# pc_healthypi_move_nRF5340_v3.net
KiCad netlist of a schematic drawn in EAGLE
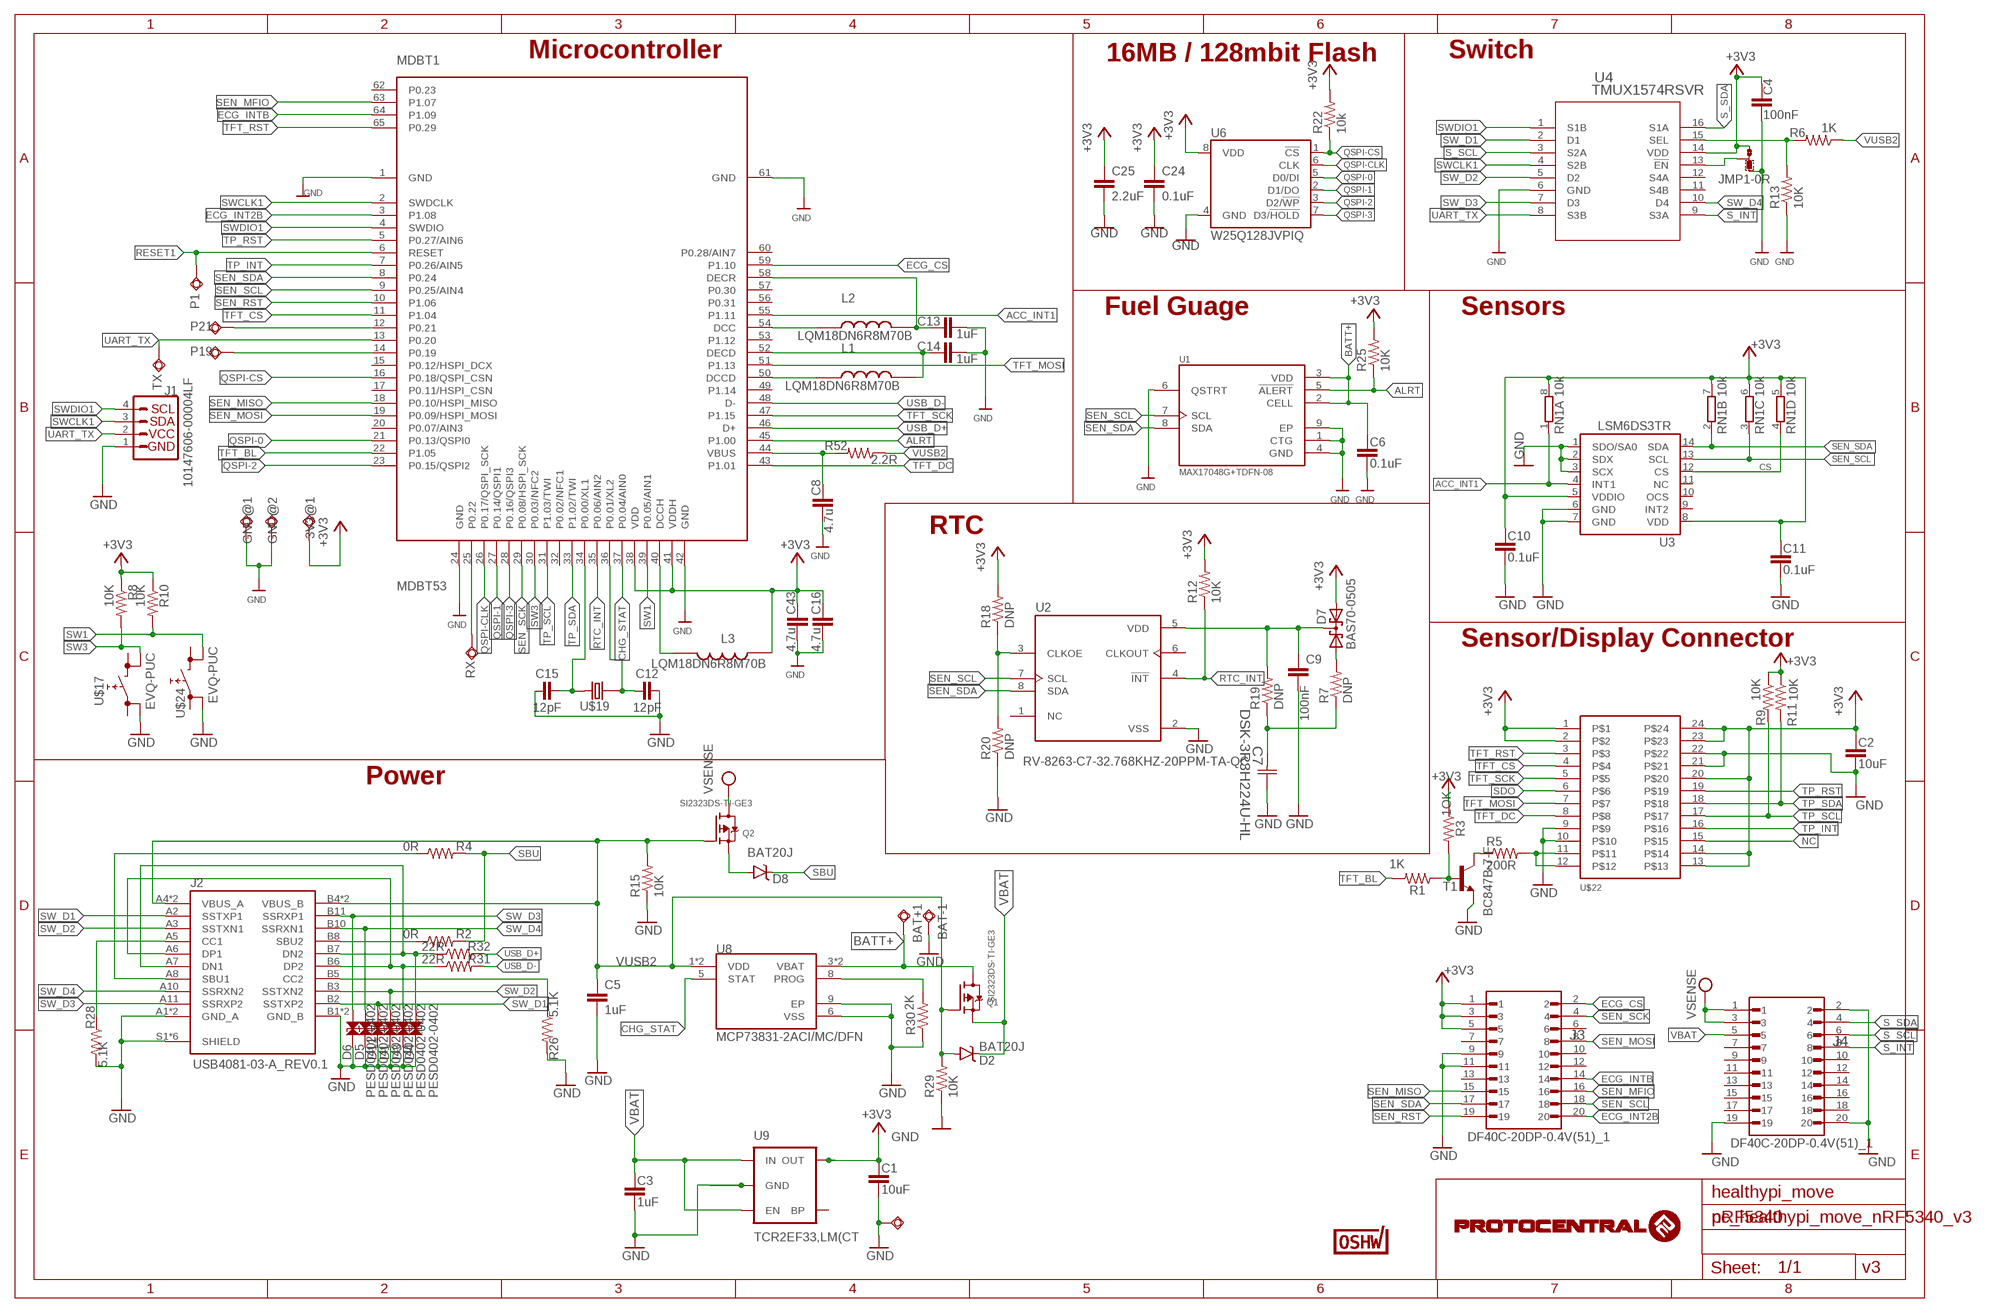
[diagram p0: schematic, sheet 1]

(export (version "E")
  (design (tool "Eeschema 10.0.6"))
  (components
    (comp (ref "3V3@1")
      (value "TPSQTP13SQ")
      (footprint "eagle-import:TP13SQ")
      (libsource (lib "eagle-import") (part "TPSQTP13SQ"))
    )
    (comp (ref "BAT+1")
      (value "TPSQTP13SQ")
      (footprint "eagle-import:TP13SQ")
      (libsource (lib "eagle-import") (part "TPSQTP13SQ"))
    )
    (comp (ref "BAT-1")
      (value "TPSQTP13SQ")
      (footprint "eagle-import:TP13SQ")
      (libsource (lib "eagle-import") (part "TPSQTP13SQ"))
    )
    (comp (ref "C1")
      (value "10uF")
      (footprint "eagle-import:0603@1")
      (libsource (lib "eagle-import") (part "0.1UF-0603-100V-10%"))
    )
    (comp (ref "C2")
      (value "10uF")
      (footprint "eagle-import:0603@1")
      (libsource (lib "eagle-import") (part "0.1UF-0603-100V-10%"))
    )
    (comp (ref "C3")
      (value "1uF")
      (footprint "eagle-import:0402-TIGHT")
      (libsource (lib "eagle-import") (part "0.1UF-0402T-6.3V-10%-X7R"))
    )
    (comp (ref "C4")
      (value "100nF")
      (footprint "eagle-import:0402-TIGHT")
      (libsource (lib "eagle-import") (part "2.2UF-0402_TIGHT-10V-10%-X5R"))
    )
    (comp (ref "C5")
      (value "1uF")
      (footprint "eagle-import:0402-TIGHT")
      (libsource (lib "eagle-import") (part "2.2UF-0402_TIGHT-10V-10%-X5R"))
    )
    (comp (ref "C6")
      (value "0.1uF")
      (footprint "eagle-import:0402-TIGHT")
      (libsource (lib "eagle-import") (part "0.1UF-0402T-6.3V-10%-X7R"))
    )
    (comp (ref "C7")
      (value "DSK-3R3H224U-HL")
      (footprint "eagle-import:CAP_DSK-3R3H224U-HL_ELN")
      (fields (field (name "COPYRIGHT") "Copyright (C) 2023 Ultra Librarian. All rights reserved."))
      (libsource (lib "eagle-import") (part "DSK-3R3H224U-HL"))
    )
    (comp (ref "C8")
      (value "4.7u")
      (footprint "eagle-import:C0402")
      (libsource (lib "eagle-import") (part "C-EUC0402"))
    )
    (comp (ref "C9")
      (value "100nF")
      (footprint "eagle-import:C0402")
      (libsource (lib "eagle-import") (part "C-EUC0402"))
    )
    (comp (ref "C10")
      (value "0.1uF")
      (footprint "eagle-import:0402-TIGHT")
      (libsource (lib "eagle-import") (part "0.1UF-0402T-6.3V-10%-X7R"))
    )
    (comp (ref "C11")
      (value "0.1uF")
      (footprint "eagle-import:0402-TIGHT")
      (libsource (lib "eagle-import") (part "0.1UF-0402T-6.3V-10%-X7R"))
    )
    (comp (ref "C12")
      (value "12pF")
      (footprint "eagle-import:C0402")
      (libsource (lib "eagle-import") (part "CAPACITORS-0402"))
    )
    (comp (ref "C13")
      (value "1uF")
      (footprint "eagle-import:0402-TIGHT")
      (libsource (lib "eagle-import") (part "2.2UF-0402_TIGHT-10V-10%-X5R"))
    )
    (comp (ref "C14")
      (value "1uF")
      (footprint "eagle-import:0402-TIGHT")
      (libsource (lib "eagle-import") (part "2.2UF-0402_TIGHT-10V-10%-X5R"))
    )
    (comp (ref "C15")
      (value "12pF")
      (footprint "eagle-import:C0402")
      (libsource (lib "eagle-import") (part "CAPACITORS-0402"))
    )
    (comp (ref "C16")
      (value "4.7u")
      (footprint "eagle-import:C0402")
      (libsource (lib "eagle-import") (part "C-EUC0402"))
    )
    (comp (ref "C24")
      (value "0.1uF")
      (footprint "eagle-import:0402-TIGHT")
      (libsource (lib "eagle-import") (part "0.1UF-0402T-6.3V-10%-X7R"))
    )
    (comp (ref "C25")
      (value "2.2uF")
      (footprint "eagle-import:0402-TIGHT")
      (libsource (lib "eagle-import") (part "2.2UF-0402_TIGHT-10V-10%-X5R"))
    )
    (comp (ref "C43")
      (value "4.7u")
      (footprint "eagle-import:C0402")
      (libsource (lib "eagle-import") (part "C-EUC0402"))
    )
    (comp (ref "D1")
      (value "PESD0402-0402")
      (footprint "eagle-import:0402")
      (fields
        (field (name "DIGIKEY_PART") "PESD0402-140CT-ND")
        (field (name "MOUSE_PART") "650-PESD0402-140")
      )
      (libsource (lib "eagle-import") (part "PESD0402-0402"))
    )
    (comp (ref "D2")
      (value "BAT20J")
      (footprint "eagle-import:SOD-323")
      (libsource (lib "eagle-import") (part "DIODE-SCHOTTKY-BAT20J"))
    )
    (comp (ref "D3")
      (value "PESD0402-0402")
      (footprint "eagle-import:0402")
      (fields
        (field (name "DIGIKEY_PART") "PESD0402-140CT-ND")
        (field (name "MOUSE_PART") "650-PESD0402-140")
      )
      (libsource (lib "eagle-import") (part "PESD0402-0402"))
    )
    (comp (ref "D4")
      (value "PESD0402-0402")
      (footprint "eagle-import:0402")
      (fields
        (field (name "DIGIKEY_PART") "PESD0402-140CT-ND")
        (field (name "MOUSE_PART") "650-PESD0402-140")
      )
      (libsource (lib "eagle-import") (part "PESD0402-0402"))
    )
    (comp (ref "D5")
      (value "PESD0402-0402")
      (footprint "eagle-import:0402")
      (fields
        (field (name "DIGIKEY_PART") "PESD0402-140CT-ND")
        (field (name "MOUSE_PART") "650-PESD0402-140")
      )
      (libsource (lib "eagle-import") (part "PESD0402-0402"))
    )
    (comp (ref "D6")
      (value "PESD0402-0402")
      (footprint "eagle-import:0402")
      (fields
        (field (name "DIGIKEY_PART") "PESD0402-140CT-ND")
        (field (name "MOUSE_PART") "650-PESD0402-140")
      )
      (libsource (lib "eagle-import") (part "PESD0402-0402"))
    )
    (comp (ref "D7")
      (value "BAS70-0505")
      (footprint "eagle-import:SOT23")
      (fields (field (name "MF") "Diotec") (field (name "MP") "BAS70-05"))
      (libsource (lib "eagle-import") (part "BAS70-0505"))
    )
    (comp (ref "D8")
      (value "BAT20J")
      (footprint "eagle-import:SOD-323")
      (libsource (lib "eagle-import") (part "DIODE-SCHOTTKY-BAT20J"))
    )
    (comp (ref "D11")
      (value "PESD0402-0402")
      (footprint "eagle-import:0402")
      (fields
        (field (name "DIGIKEY_PART") "PESD0402-140CT-ND")
        (field (name "MOUSE_PART") "650-PESD0402-140")
      )
      (libsource (lib "eagle-import") (part "PESD0402-0402"))
    )
    (comp (ref "GND@1")
      (value "TPSQTP13SQ")
      (footprint "eagle-import:TP13SQ")
      (libsource (lib "eagle-import") (part "TPSQTP13SQ"))
    )
    (comp (ref "GND@2")
      (value "TPSQTP13SQ")
      (footprint "eagle-import:TP13SQ")
      (libsource (lib "eagle-import") (part "TPSQTP13SQ"))
    )
    (comp (ref "J1")
      (value "10147606-00004LF")
      (footprint "eagle-import:JST04_1MM_RA")
      (libsource (lib "eagle-import") (part "QWIIC_CONNECTORJS-1MM"))
    )
    (comp (ref "J2")
      (value "USB4081-03-A_REV0.1")
      (footprint "eagle-import:GCT_USB4081-03-A_REV0.1")
      (fields (field (name "MF") "Global Connector Technology") (field (name "MP") "USB4081-03-A"))
      (libsource (lib "eagle-import") (part "USB4081-03-A_REV0.1"))
    )
    (comp (ref "J3")
      (value "DF40C-20DP-0.4V(51)_1")
      (footprint "eagle-import:HRS_DF40C-20DP-0.4V(51)")
      (fields (field (name "MANUFACTURER") "Hirose Electric"))
      (libsource (lib "eagle-import") (part "DF40C-20DP-0.4V(51)_1"))
    )
    (comp (ref "J4")
      (value "DF40C-20DP-0.4V(51)_1")
      (footprint "eagle-import:HRS_DF40C-20DP-0.4V(51)")
      (fields (field (name "MANUFACTURER") "Hirose Electric"))
      (libsource (lib "eagle-import") (part "DF40C-20DP-0.4V(51)_1"))
    )
    (comp (ref "JMP1")
      (value "0R-JUMPB")
      (footprint "eagle-import:B0R-JMP")
      (libsource (lib "eagle-import") (part "0R-JUMPB"))
    )
    (comp (ref "L1")
      (value "LQM18DN6R8M70B")
      (footprint "eagle-import:INDC1608X95N")
      (fields (field (name "MF") "Murata"))
      (libsource (lib "eagle-import") (part "LQM18DN6R8M70B"))
    )
    (comp (ref "L2")
      (value "LQM18DN6R8M70B")
      (footprint "eagle-import:INDC1608X95N")
      (fields (field (name "MF") "Murata"))
      (libsource (lib "eagle-import") (part "LQM18DN6R8M70B"))
    )
    (comp (ref "L3")
      (value "LQM18DN6R8M70B")
      (footprint "eagle-import:INDC1608X95N")
      (fields (field (name "MF") "Murata"))
      (libsource (lib "eagle-import") (part "LQM18DN6R8M70B"))
    )
    (comp (ref "MDBT1")
      (value "MDBT53")
      (footprint "eagle-import:MDBT53")
      (libsource (lib "eagle-import") (part "MDBT53"))
    )
    (comp (ref "P1")
      (value "TPSQTP13SQ")
      (footprint "eagle-import:TP13SQ")
      (libsource (lib "eagle-import") (part "TPSQTP13SQ"))
    )
    (comp (ref "P19")
      (value "TPSQTP13SQ")
      (footprint "eagle-import:TP13SQ")
      (libsource (lib "eagle-import") (part "TPSQTP13SQ"))
    )
    (comp (ref "P21")
      (value "TPSQTP13SQ")
      (footprint "eagle-import:TP13SQ")
      (libsource (lib "eagle-import") (part "TPSQTP13SQ"))
    )
    (comp (ref "Q1")
      (value "SI2323DS-TI-GE3")
      (footprint "eagle-import:SOT23-R")
      (libsource (lib "eagle-import") (part "MOSFET-P"))
    )
    (comp (ref "Q2")
      (value "SI2323DS-TI-GE3")
      (footprint "eagle-import:SOT23-R")
      (libsource (lib "eagle-import") (part "MOSFET-P"))
    )
    (comp (ref "R1")
      (value "200")
      (footprint "eagle-import:R0402")
      (libsource (lib "eagle-import") (part "R-US_R0402"))
    )
    (comp (ref "R2")
      (value "0R")
      (footprint "eagle-import:0402-RES")
      (libsource (lib "eagle-import") (part "RESISTOR0402-RES"))
    )
    (comp (ref "R3")
      (value "200")
      (footprint "eagle-import:R0402")
      (libsource (lib "eagle-import") (part "R-US_R0402"))
    )
    (comp (ref "R4")
      (value "0R")
      (footprint "eagle-import:0402-RES")
      (libsource (lib "eagle-import") (part "RESISTOR0402-RES"))
    )
    (comp (ref "R5")
      (value "200R")
      (footprint "eagle-import:R0402")
      (libsource (lib "eagle-import") (part "R-US_R0402"))
    )
    (comp (ref "R6")
      (value "1K")
      (footprint "eagle-import:0402-RES")
      (libsource (lib "eagle-import") (part "RESISTOR0402-RES"))
    )
    (comp (ref "R7")
      (value "DNP")
      (footprint "eagle-import:R0402")
      (libsource (lib "eagle-import") (part "R-US_R0402"))
    )
    (comp (ref "R8")
      (value "10K")
      (footprint "eagle-import:R0402")
      (libsource (lib "eagle-import") (part "R-US_R0402"))
    )
    (comp (ref "R9")
      (value "10K")
      (footprint "eagle-import:R0402")
      (libsource (lib "eagle-import") (part "R-US_R0402"))
    )
    (comp (ref "R10")
      (value "10K")
      (footprint "eagle-import:R0402")
      (libsource (lib "eagle-import") (part "R-US_R0402"))
    )
    (comp (ref "R11")
      (value "10K")
      (footprint "eagle-import:R0402")
      (libsource (lib "eagle-import") (part "R-US_R0402"))
    )
    (comp (ref "R12")
      (value "10K")
      (footprint "eagle-import:R0402")
      (libsource (lib "eagle-import") (part "R-US_R0402"))
    )
    (comp (ref "R13")
      (value "10K")
      (footprint "eagle-import:R0402")
      (libsource (lib "eagle-import") (part "R-US_R0402"))
    )
    (comp (ref "R15")
      (value "10K")
      (footprint "eagle-import:R0402")
      (libsource (lib "eagle-import") (part "R-US_R0402"))
    )
    (comp (ref "R18")
      (value "DNP")
      (footprint "eagle-import:R0402")
      (libsource (lib "eagle-import") (part "R-US_R0402"))
    )
    (comp (ref "R19")
      (value "DNP")
      (footprint "eagle-import:R0402")
      (libsource (lib "eagle-import") (part "R-US_R0402"))
    )
    (comp (ref "R20")
      (value "DNP")
      (footprint "eagle-import:R0402")
      (libsource (lib "eagle-import") (part "R-US_R0402"))
    )
    (comp (ref "R22")
      (value "10k")
      (footprint "eagle-import:R0402")
      (libsource (lib "eagle-import") (part "R-US_R0402"))
    )
    (comp (ref "R25")
      (value "10K")
      (footprint "eagle-import:0402-RES")
      (libsource (lib "eagle-import") (part "RESISTOR0402-RES"))
    )
    (comp (ref "R26")
      (value "5.1K")
      (footprint "eagle-import:0402-RES")
      (libsource (lib "eagle-import") (part "RESISTOR0402-RES"))
    )
    (comp (ref "R28")
      (value "5.1K")
      (footprint "eagle-import:0402-RES")
      (libsource (lib "eagle-import") (part "RESISTOR0402-RES"))
    )
    (comp (ref "R29")
      (value "10K")
      (footprint "eagle-import:R0402")
      (libsource (lib "eagle-import") (part "R-US_R0402"))
    )
    (comp (ref "R30")
      (value "2K")
      (footprint "eagle-import:R0402")
      (libsource (lib "eagle-import") (part "R-US_R0402"))
    )
    (comp (ref "R31")
      (value "22R")
      (footprint "eagle-import:0402-RES")
      (libsource (lib "eagle-import") (part "RESISTOR0402-RES"))
    )
    (comp (ref "R32")
      (value "22R")
      (footprint "eagle-import:0402-RES")
      (libsource (lib "eagle-import") (part "RESISTOR0402-RES"))
    )
    (comp (ref "R52")
      (value "2.2R")
      (footprint "eagle-import:0402-RES")
      (libsource (lib "eagle-import") (part "RESISTOR0402-RES"))
    )
    (comp (ref "RN1")
      (value "10k")
      (footprint "eagle-import:4X0402ARV341")
      (libsource (lib "eagle-import") (part "4R-N0402ARV341"))
    )
    (comp (ref "RX")
      (value "TPSQTP13SQ")
      (footprint "eagle-import:TP13SQ")
      (libsource (lib "eagle-import") (part "TPSQTP13SQ"))
    )
    (comp (ref "SWIO6")
      (value "TPSQTP11R")
      (footprint "eagle-import:TP11R")
      (libsource (lib "eagle-import") (part "TPSQTP11R"))
    )
    (comp (ref "T1")
      (value "BC847B-7-F")
      (footprint "eagle-import:SOT23-BEC")
      (libsource (lib "eagle-import") (part "-NPN-SOT23-BECMMBT2222ALT1"))
    )
    (comp (ref "TX")
      (value "TPSQTP13SQ")
      (footprint "eagle-import:TP13SQ")
      (libsource (lib "eagle-import") (part "TPSQTP13SQ"))
    )
    (comp (ref "U$9")
      (value "CERT-SMALL")
      (footprint "eagle-import:CERT-SMALL-SILK")
      (libsource (lib "eagle-import") (part "CERT-SMALL"))
    )
    (comp (ref "U$17")
      (value "EVQ-PUC")
      (footprint "eagle-import:EVQ-PUC")
      (libsource (lib "eagle-import") (part "EVQ-PUC"))
    )
    (comp (ref "U$19")
      (value "520-327-12.5-34B(32.768KHZ)")
      (footprint "eagle-import:ECX-31B")
      (libsource (lib "eagle-import") (part "ECS-X-34B"))
    )
    (comp (ref "U$22")
      (value "AXT524124")
      (footprint "eagle-import:AXT524124")
      (libsource (lib "eagle-import") (part "AXT524124"))
    )
    (comp (ref "U$24")
      (value "EVQ-PUC")
      (footprint "eagle-import:EVQ-PUC")
      (libsource (lib "eagle-import") (part "EVQ-PUC"))
    )
    (comp (ref "U1")
      (value "MAX17048G+TDFN-08")
      (footprint "eagle-import:SON50P200X200X80-9N")
      (fields (field (name "MF") "Analog Devices") (field (name "MP") "MAX17048G+"))
      (libsource (lib "eagle-import") (part "MAX17048G+TDFN-08"))
    )
    (comp (ref "U2")
      (value "RV-8263-C7-32.768KHZ-20PPM-TA-QC")
      (footprint "eagle-import:IC_RV-8263-C7-32.768KHZ-20PPM-TA-QC")
      (fields (field (name "MF") "Micro Crystal"))
      (libsource (lib "eagle-import") (part "RV-8263-C7-32.768KHZ-20PPM-TA-QC"))
    )
    (comp (ref "U3")
      (value "LSM6DS3TR")
      (footprint "eagle-import:LGA14L")
      (libsource (lib "eagle-import") (part "LSM6DS3"))
    )
    (comp (ref "U4")
      (value "TMUX1574RSVR")
      (footprint "eagle-import:RSV16_TEX")
      (fields (field (name "COPYRIGHT") "Copyright (C) 2024 Ultra Librarian. All rights reserved."))
      (libsource (lib "eagle-import") (part "TMUX1574RSVR"))
    )
    (comp (ref "U6")
      (value "W25Q128JVPIQ")
      (footprint "eagle-import:WSON-8-6X5-SKINNY_CENTERPAD")
      (libsource (lib "eagle-import") (part "W25QXX128MBIT-6X5-SKINNY_CENTER"))
    )
    (comp (ref "U8")
      (value "MCP73831-2ACI/MC/DFN")
      (footprint "eagle-import:SON50P200X300X100-9N")
      (fields (field (name "MF") "Microchip Technology") (field (name "MP") "MCP73831-2ACI/MC"))
      (libsource (lib "eagle-import") (part "MCP73831-2ACI/MC/DFN"))
    )
    (comp (ref "U9")
      (value "TCR2EF33,LM(CT")
      (footprint "eagle-import:SOT23-5")
      (libsource (lib "eagle-import") (part "V_REG_LDOSMD"))
    )
  )
  (nets
    (net (code "1") (name "+3V3") (class "Default")
      (node (ref "3V3@1") (pin "TP") (pinfunction "TP_TP") (pintype "input"))
      (node (ref "C1") (pin "1") (pinfunction "1_1") (pintype "passive"))
      (node (ref "C10") (pin "1") (pinfunction "1_1") (pintype "passive"))
      (node (ref "C11") (pin "1") (pinfunction "1_1") (pintype "passive"))
      (node (ref "C16") (pin "1") (pinfunction "1_1") (pintype "passive"))
      (node (ref "C2") (pin "1") (pinfunction "1_1") (pintype "passive"))
      (node (ref "C24") (pin "1") (pinfunction "1_1") (pintype "passive"))
      (node (ref "C25") (pin "1") (pinfunction "1_1") (pintype "passive"))
      (node (ref "C4") (pin "1") (pinfunction "1_1") (pintype "passive"))
      (node (ref "C43") (pin "1") (pinfunction "1_1") (pintype "passive"))
      (node (ref "D7") (pin "2") (pinfunction "A2_2") (pintype "passive"))
      (node (ref "J3") (pin "1") (pinfunction "1_1") (pintype "passive"))
      (node (ref "J3") (pin "3") (pinfunction "3_3") (pintype "passive"))
      (node (ref "J3") (pin "5") (pinfunction "5_5") (pintype "passive"))
      (node (ref "JMP1") (pin "3") (pinfunction "3_3") (pintype "passive"))
      (node (ref "L3") (pin "1") (pinfunction "1_1") (pintype "passive"))
      (node (ref "MDBT1") (pin "38") (pinfunction "VDD_38") (pintype "bidirectional"))
      (node (ref "MDBT1") (pin "41") (pinfunction "VDDH_41") (pintype "bidirectional"))
      (node (ref "R10") (pin "1") (pinfunction "1_1") (pintype "passive"))
      (node (ref "R11") (pin "1") (pinfunction "1_1") (pintype "passive"))
      (node (ref "R12") (pin "2") (pinfunction "2_2") (pintype "passive"))
      (node (ref "R18") (pin "2") (pinfunction "2_2") (pintype "passive"))
      (node (ref "R22") (pin "2") (pinfunction "2_2") (pintype "passive"))
      (node (ref "R25") (pin "2") (pinfunction "2_2") (pintype "passive"))
      (node (ref "R3") (pin "1") (pinfunction "1_1") (pintype "passive"))
      (node (ref "R8") (pin "1") (pinfunction "1_1") (pintype "passive"))
      (node (ref "R9") (pin "1") (pinfunction "1_1") (pintype "passive"))
      (node (ref "RN1") (pin "5") (pinfunction "2_5") (pintype "passive"))
      (node (ref "RN1") (pin "6") (pinfunction "2_6") (pintype "passive"))
      (node (ref "RN1") (pin "7") (pinfunction "2_7") (pintype "passive"))
      (node (ref "RN1") (pin "8") (pinfunction "2_8") (pintype "passive"))
      (node (ref "U$22") (pin "1") (pinfunction "P$1_1") (pintype "bidirectional"))
      (node (ref "U$22") (pin "13") (pinfunction "P$13_13") (pintype "bidirectional"))
      (node (ref "U$22") (pin "14") (pinfunction "P$14_14") (pintype "bidirectional"))
      (node (ref "U$22") (pin "2") (pinfunction "P$2_2") (pintype "bidirectional"))
      (node (ref "U$22") (pin "20") (pinfunction "P$20_20") (pintype "bidirectional"))
      (node (ref "U$22") (pin "23") (pinfunction "P$23_23") (pintype "bidirectional"))
      (node (ref "U$22") (pin "24") (pinfunction "P$24_24") (pintype "bidirectional"))
      (node (ref "U3") (pin "5") (pinfunction "VDDIO_5") (pintype "bidirectional"))
      (node (ref "U3") (pin "8") (pinfunction "VDD_8") (pintype "bidirectional"))
      (node (ref "U4") (pin "14") (pinfunction "VDD_14") (pintype "power_in"))
      (node (ref "U6") (pin "8") (pinfunction "VDD_8") (pintype "bidirectional"))
      (node (ref "U9") (pin "5") (pinfunction "OUT_5") (pintype "passive"))
    )
    (net (code "2") (name "/CS") (class "Default")
      (node (ref "RN1") (pin "4") (pinfunction "1_4") (pintype "passive"))
      (node (ref "U3") (pin "12") (pinfunction "CS_12") (pintype "bidirectional"))
    )
    (net (code "3") (name "ACC_INT1") (class "Default")
      (node (ref "MDBT1") (pin "55") (pinfunction "P1.11_55") (pintype "bidirectional"))
      (node (ref "RN1") (pin "1") (pinfunction "1_1") (pintype "passive"))
      (node (ref "U3") (pin "4") (pinfunction "INT1_4") (pintype "bidirectional"))
    )
    (net (code "4") (name "ALRT") (class "Default")
      (node (ref "MDBT1") (pin "45") (pinfunction "P1.00_45") (pintype "bidirectional"))
      (node (ref "R25") (pin "1") (pinfunction "1_1") (pintype "passive"))
      (node (ref "U1") (pin "5") (pinfunction "~{ALERT}_5") (pintype "output"))
    )
    (net (code "5") (name "BATT+") (class "Default")
      (node (ref "BAT+1") (pin "TP") (pinfunction "TP_TP") (pintype "input"))
      (node (ref "C6") (pin "1") (pinfunction "1_1") (pintype "passive"))
      (node (ref "Q1") (pin "3") (pinfunction "D_3") (pintype "passive"))
      (node (ref "U1") (pin "2") (pinfunction "CELL_2") (pintype "power_in"))
      (node (ref "U1") (pin "3") (pinfunction "VDD_3") (pintype "power_in"))
      (node (ref "U8") (pin "3") (pinfunction "VBAT_3") (pintype "output"))
      (node (ref "U8") (pin "4") (pinfunction "VBAT_4") (pintype "output"))
    )
    (net (code "6") (name "CHG_STAT") (class "Default")
      (node (ref "MDBT1") (pin "37") (pinfunction "P0.04/AIN0_37") (pintype "bidirectional"))
      (node (ref "U8") (pin "5") (pinfunction "STAT_5") (pintype "output"))
    )
    (net (code "7") (name "ECG_CS") (class "Default")
      (node (ref "J3") (pin "2") (pinfunction "2_2") (pintype "passive"))
      (node (ref "MDBT1") (pin "59") (pinfunction "P1.10_59") (pintype "bidirectional"))
    )
    (net (code "8") (name "ECG_INT2B") (class "Default")
      (node (ref "J3") (pin "20") (pinfunction "20_20") (pintype "passive"))
      (node (ref "MDBT1") (pin "3") (pinfunction "P1.08_3") (pintype "bidirectional"))
    )
    (net (code "9") (name "ECG_INTB") (class "Default")
      (node (ref "J3") (pin "14") (pinfunction "14_14") (pintype "passive"))
      (node (ref "MDBT1") (pin "64") (pinfunction "P1.09_64") (pintype "bidirectional"))
    )
    (net (code "10") (name "GND") (class "Default")
      (node (ref "BAT-1") (pin "TP") (pinfunction "TP_TP") (pintype "input"))
      (node (ref "C1") (pin "2") (pinfunction "2_2") (pintype "passive"))
      (node (ref "C10") (pin "2") (pinfunction "2_2") (pintype "passive"))
      (node (ref "C11") (pin "2") (pinfunction "2_2") (pintype "passive"))
      (node (ref "C12") (pin "2") (pinfunction "2_2") (pintype "passive"))
      (node (ref "C13") (pin "2") (pinfunction "2_2") (pintype "passive"))
      (node (ref "C14") (pin "2") (pinfunction "2_2") (pintype "passive"))
      (node (ref "C15") (pin "1") (pinfunction "1_1") (pintype "passive"))
      (node (ref "C16") (pin "2") (pinfunction "2_2") (pintype "passive"))
      (node (ref "C2") (pin "2") (pinfunction "2_2") (pintype "passive"))
      (node (ref "C24") (pin "2") (pinfunction "2_2") (pintype "passive"))
      (node (ref "C25") (pin "2") (pinfunction "2_2") (pintype "passive"))
      (node (ref "C3") (pin "2") (pinfunction "2_2") (pintype "passive"))
      (node (ref "C4") (pin "2") (pinfunction "2_2") (pintype "passive"))
      (node (ref "C43") (pin "2") (pinfunction "2_2") (pintype "passive"))
      (node (ref "C5") (pin "2") (pinfunction "2_2") (pintype "passive"))
      (node (ref "C6") (pin "2") (pinfunction "2_2") (pintype "passive"))
      (node (ref "C7") (pin "1") (pinfunction "1_1") (pintype "passive"))
      (node (ref "C8") (pin "2") (pinfunction "2_2") (pintype "passive"))
      (node (ref "C9") (pin "2") (pinfunction "2_2") (pintype "passive"))
      (node (ref "D1") (pin "1") (pinfunction "1_1") (pintype "bidirectional"))
      (node (ref "D11") (pin "1") (pinfunction "1_1") (pintype "bidirectional"))
      (node (ref "D3") (pin "1") (pinfunction "1_1") (pintype "bidirectional"))
      (node (ref "D4") (pin "1") (pinfunction "1_1") (pintype "bidirectional"))
      (node (ref "D5") (pin "1") (pinfunction "1_1") (pintype "bidirectional"))
      (node (ref "D6") (pin "1") (pinfunction "1_1") (pintype "bidirectional"))
      (node (ref "GND@1") (pin "TP") (pinfunction "TP_TP") (pintype "input"))
      (node (ref "GND@2") (pin "TP") (pinfunction "TP_TP") (pintype "input"))
      (node (ref "J1") (pin "1") (pinfunction "1_1") (pintype "power_in"))
      (node (ref "J2") (pin "A1") (pinfunction "GND_A_A1") (pintype "power_in"))
      (node (ref "J2") (pin "A12") (pinfunction "GND_A_A12") (pintype "power_in"))
      (node (ref "J2") (pin "B1") (pinfunction "GND_B_B1") (pintype "power_in"))
      (node (ref "J2") (pin "B12") (pinfunction "GND_B_B12") (pintype "power_in"))
      (node (ref "J2") (pin "S1") (pinfunction "SHIELD_S1") (pintype "passive"))
      (node (ref "J2") (pin "S2") (pinfunction "SHIELD_S2") (pintype "passive"))
      (node (ref "J2") (pin "S3") (pinfunction "SHIELD_S3") (pintype "passive"))
      (node (ref "J2") (pin "S4") (pinfunction "SHIELD_S4") (pintype "passive"))
      (node (ref "J2") (pin "S5") (pinfunction "SHIELD_S5") (pintype "passive"))
      (node (ref "J2") (pin "S6") (pinfunction "SHIELD_S6") (pintype "passive"))
      (node (ref "J3") (pin "11") (pinfunction "11_11") (pintype "passive"))
      (node (ref "J3") (pin "9") (pinfunction "9_9") (pintype "passive"))
      (node (ref "J4") (pin "19") (pinfunction "19_19") (pintype "passive"))
      (node (ref "J4") (pin "2") (pinfunction "2_2") (pintype "passive"))
      (node (ref "J4") (pin "20") (pinfunction "20_20") (pintype "passive"))
      (node (ref "JMP1") (pin "1") (pinfunction "1_1") (pintype "passive"))
      (node (ref "MDBT1") (pin "1") (pinfunction "GND_1") (pintype "bidirectional"))
      (node (ref "MDBT1") (pin "24") (pinfunction "GND_24") (pintype "bidirectional"))
      (node (ref "MDBT1") (pin "42") (pinfunction "GND_42") (pintype "bidirectional"))
      (node (ref "MDBT1") (pin "61") (pinfunction "GND_61") (pintype "bidirectional"))
      (node (ref "R13") (pin "1") (pinfunction "1_1") (pintype "passive"))
      (node (ref "R15") (pin "1") (pinfunction "1_1") (pintype "passive"))
      (node (ref "R20") (pin "1") (pinfunction "1_1") (pintype "passive"))
      (node (ref "R26") (pin "2") (pinfunction "2_2") (pintype "passive"))
      (node (ref "R28") (pin "2") (pinfunction "2_2") (pintype "passive"))
      (node (ref "R29") (pin "1") (pinfunction "1_1") (pintype "passive"))
      (node (ref "R30") (pin "1") (pinfunction "1_1") (pintype "passive"))
      (node (ref "SWIO6") (pin "TP") (pinfunction "TP_TP") (pintype "input"))
      (node (ref "T1") (pin "E") (pinfunction "E_E") (pintype "passive"))
      (node (ref "U$17") (pin "3") (pinfunction "0_3") (pintype "passive"))
      (node (ref "U$22") (pin "10") (pinfunction "P$10_10") (pintype "bidirectional"))
      (node (ref "U$22") (pin "21") (pinfunction "P$21_21") (pintype "bidirectional"))
      (node (ref "U$22") (pin "22") (pinfunction "P$22_22") (pintype "bidirectional"))
      (node (ref "U$22") (pin "9") (pinfunction "P$9_9") (pintype "bidirectional"))
      (node (ref "U$24") (pin "3") (pinfunction "0_3") (pintype "passive"))
      (node (ref "U1") (pin "1") (pinfunction "CTG_1") (pintype "power_in"))
      (node (ref "U1") (pin "4") (pinfunction "GND_4") (pintype "power_in"))
      (node (ref "U1") (pin "6") (pinfunction "QSTRT_6") (pintype "input"))
      (node (ref "U1") (pin "9") (pinfunction "EP_9") (pintype "power_in"))
      (node (ref "U2") (pin "2") (pinfunction "VSS_2") (pintype "power_in"))
      (node (ref "U3") (pin "1") (pinfunction "SDO/SA0_1") (pintype "bidirectional"))
      (node (ref "U3") (pin "2") (pinfunction "SDX_2") (pintype "bidirectional"))
      (node (ref "U3") (pin "3") (pinfunction "SCX_3") (pintype "bidirectional"))
      (node (ref "U3") (pin "6") (pinfunction "GND_6") (pintype "bidirectional"))
      (node (ref "U3") (pin "7") (pinfunction "GND_7") (pintype "bidirectional"))
      (node (ref "U4") (pin "6") (pinfunction "GND_6") (pintype "passive"))
      (node (ref "U6") (pin "4") (pinfunction "GND_4") (pintype "bidirectional"))
      (node (ref "U8") (pin "6") (pinfunction "VSS_6") (pintype "power_in"))
      (node (ref "U8") (pin "9") (pinfunction "EP_9") (pintype "power_in"))
      (node (ref "U9") (pin "2") (pinfunction "GND_2") (pintype "input"))
    )
    (net (code "11") (name "NC") (class "Default")
      (node (ref "U$22") (pin "15") (pinfunction "P$15_15") (pintype "bidirectional"))
    )
    (net (code "12") (name "Net-(C7-Pad2)") (class "Default")
      (node (ref "C7") (pin "2") (pinfunction "2_2") (pintype "passive"))
      (node (ref "R19") (pin "1") (pinfunction "1_1") (pintype "passive"))
      (node (ref "R7") (pin "1") (pinfunction "1_1") (pintype "passive"))
    )
    (net (code "13") (name "Net-(D7-A1)") (class "Default")
      (node (ref "D7") (pin "1") (pinfunction "A1_1") (pintype "passive"))
      (node (ref "R7") (pin "2") (pinfunction "2_2") (pintype "passive"))
    )
    (net (code "14") (name "Net-(D7-K1K2)") (class "Default")
      (node (ref "C9") (pin "1") (pinfunction "1_1") (pintype "passive"))
      (node (ref "D7") (pin "3") (pinfunction "K1K2_3") (pintype "passive"))
      (node (ref "R19") (pin "2") (pinfunction "2_2") (pintype "passive"))
      (node (ref "U2") (pin "5") (pinfunction "VDD_5") (pintype "power_in"))
    )
    (net (code "15") (name "Net-(J2-CC1)") (class "Default")
      (node (ref "J2") (pin "A5") (pinfunction "CC1_A5") (pintype "bidirectional"))
      (node (ref "R28") (pin "1") (pinfunction "1_1") (pintype "passive"))
    )
    (net (code "16") (name "Net-(J2-CC2)") (class "Default")
      (node (ref "J2") (pin "B5") (pinfunction "CC2_B5") (pintype "bidirectional"))
      (node (ref "R26") (pin "1") (pinfunction "1_1") (pintype "passive"))
    )
    (net (code "17") (name "Net-(J2-DN1)") (class "Default")
      (node (ref "D4") (pin "2") (pinfunction "2_2") (pintype "bidirectional"))
      (node (ref "J2") (pin "A7") (pinfunction "DN1_A7") (pintype "bidirectional"))
      (node (ref "J2") (pin "B7") (pinfunction "DN2_B7") (pintype "bidirectional"))
      (node (ref "R32") (pin "1") (pinfunction "1_1") (pintype "passive"))
    )
    (net (code "18") (name "Net-(J2-DP1)") (class "Default")
      (node (ref "D3") (pin "2") (pinfunction "2_2") (pintype "bidirectional"))
      (node (ref "J2") (pin "A6") (pinfunction "DP1_A6") (pintype "bidirectional"))
      (node (ref "J2") (pin "B6") (pinfunction "DP2_B6") (pintype "bidirectional"))
      (node (ref "R31") (pin "1") (pinfunction "1_1") (pintype "passive"))
    )
    (net (code "19") (name "Net-(J2-SBU1)") (class "Default")
      (node (ref "J2") (pin "A8") (pinfunction "SBU1_A8") (pintype "bidirectional"))
      (node (ref "R4") (pin "1") (pinfunction "1_1") (pintype "passive"))
    )
    (net (code "20") (name "Net-(J2-SBU2)") (class "Default")
      (node (ref "J2") (pin "B8") (pinfunction "SBU2_B8") (pintype "bidirectional"))
      (node (ref "R2") (pin "1") (pinfunction "1_1") (pintype "passive"))
    )
    (net (code "21") (name "Net-(MDBT1-DCC)") (class "Default")
      (node (ref "L2") (pin "1") (pinfunction "1_1") (pintype "passive"))
      (node (ref "MDBT1") (pin "54") (pinfunction "DCC_54") (pintype "bidirectional"))
    )
    (net (code "22") (name "Net-(MDBT1-DCCD)") (class "Default")
      (node (ref "L1") (pin "1") (pinfunction "1_1") (pintype "passive"))
      (node (ref "MDBT1") (pin "50") (pinfunction "DCCD_50") (pintype "bidirectional"))
    )
    (net (code "23") (name "Net-(MDBT1-DCCH)") (class "Default")
      (node (ref "L3") (pin "2") (pinfunction "2_2") (pintype "passive"))
      (node (ref "MDBT1") (pin "40") (pinfunction "DCCH_40") (pintype "bidirectional"))
    )
    (net (code "24") (name "Net-(MDBT1-DECD)") (class "Default")
      (node (ref "C14") (pin "1") (pinfunction "1_1") (pintype "passive"))
      (node (ref "L1") (pin "2") (pinfunction "2_2") (pintype "passive"))
      (node (ref "MDBT1") (pin "52") (pinfunction "DECD_52") (pintype "bidirectional"))
    )
    (net (code "25") (name "Net-(MDBT1-DECR)") (class "Default")
      (node (ref "C13") (pin "1") (pinfunction "1_1") (pintype "passive"))
      (node (ref "L2") (pin "2") (pinfunction "2_2") (pintype "passive"))
      (node (ref "MDBT1") (pin "58") (pinfunction "DECR_58") (pintype "bidirectional"))
    )
    (net (code "26") (name "Net-(MDBT1-P0.00{slash}XL1)") (class "Default")
      (node (ref "C15") (pin "2") (pinfunction "2_2") (pintype "passive"))
      (node (ref "MDBT1") (pin "34") (pinfunction "P0.00/XL1_34") (pintype "bidirectional"))
      (node (ref "U$19") (pin "P$2") (pinfunction "2_P$2") (pintype "passive"))
    )
    (net (code "27") (name "Net-(MDBT1-P0.01{slash}XL2)") (class "Default")
      (node (ref "C12") (pin "1") (pinfunction "1_1") (pintype "passive"))
      (node (ref "MDBT1") (pin "36") (pinfunction "P0.01/XL2_36") (pintype "bidirectional"))
      (node (ref "U$19") (pin "P$1") (pinfunction "1_P$1") (pintype "passive"))
    )
    (net (code "28") (name "Net-(MDBT1-P0.19)") (class "Default")
      (node (ref "MDBT1") (pin "14") (pinfunction "P0.19_14") (pintype "bidirectional"))
      (node (ref "P19") (pin "TP") (pinfunction "TP_TP") (pintype "input"))
    )
    (net (code "29") (name "Net-(MDBT1-P0.21)") (class "Default")
      (node (ref "MDBT1") (pin "12") (pinfunction "P0.21_12") (pintype "bidirectional"))
      (node (ref "P21") (pin "TP") (pinfunction "TP_TP") (pintype "input"))
    )
    (net (code "30") (name "Net-(MDBT1-P0.22)") (class "Default")
      (node (ref "MDBT1") (pin "25") (pinfunction "P0.22_25") (pintype "bidirectional"))
      (node (ref "RX") (pin "TP") (pinfunction "TP_TP") (pintype "input"))
    )
    (net (code "31") (name "Net-(MDBT1-VBUS)") (class "Default")
      (node (ref "C8") (pin "1") (pinfunction "1_1") (pintype "passive"))
      (node (ref "MDBT1") (pin "44") (pinfunction "VBUS_44") (pintype "bidirectional"))
      (node (ref "R52") (pin "2") (pinfunction "2_2") (pintype "passive"))
    )
    (net (code "32") (name "Net-(Q2-S)") (class "Default")
      (node (ref "D8") (pin "A") (pinfunction "A_A") (pintype "passive"))
      (node (ref "Q2") (pin "2") (pinfunction "S_2") (pintype "passive"))
    )
    (net (code "33") (name "Net-(R1-Pad1)") (class "Default")
      (node (ref "R1") (pin "1") (pinfunction "1_1") (pintype "passive"))
      (node (ref "R3") (pin "2") (pinfunction "2_2") (pintype "passive"))
      (node (ref "T1") (pin "B") (pinfunction "B_B") (pintype "passive"))
    )
    (net (code "34") (name "Net-(R5-Pad1)") (class "Default")
      (node (ref "R5") (pin "1") (pinfunction "1_1") (pintype "passive"))
      (node (ref "T1") (pin "C") (pinfunction "C_C") (pintype "passive"))
    )
    (net (code "35") (name "Net-(U$22-P$11)") (class "Default")
      (node (ref "R5") (pin "2") (pinfunction "2_2") (pintype "passive"))
      (node (ref "U$22") (pin "11") (pinfunction "P$11_11") (pintype "bidirectional"))
      (node (ref "U$22") (pin "12") (pinfunction "P$12_12") (pintype "bidirectional"))
    )
    (net (code "36") (name "Net-(U2-CLKOE)") (class "Default")
      (node (ref "R18") (pin "1") (pinfunction "1_1") (pintype "passive"))
      (node (ref "R20") (pin "2") (pinfunction "2_2") (pintype "passive"))
      (node (ref "U2") (pin "3") (pinfunction "CLKOE_3") (pintype "input"))
    )
    (net (code "37") (name "Net-(U4-SEL)") (class "Default")
      (node (ref "R13") (pin "2") (pinfunction "2_2") (pintype "passive"))
      (node (ref "R6") (pin "2") (pinfunction "2_2") (pintype "passive"))
      (node (ref "U4") (pin "15") (pinfunction "SEL_15") (pintype "passive"))
    )
    (net (code "38") (name "Net-(U4-~{EN})") (class "Default")
      (node (ref "JMP1") (pin "2") (pinfunction "2_2") (pintype "passive"))
      (node (ref "U4") (pin "13") (pinfunction "~{EN}_13") (pintype "passive"))
    )
    (net (code "39") (name "Net-(U8-PROG)") (class "Default")
      (node (ref "R30") (pin "2") (pinfunction "2_2") (pintype "passive"))
      (node (ref "U8") (pin "8") (pinfunction "PROG_8") (pintype "input"))
    )
    (net (code "40") (name "QSPI-0") (class "Default")
      (node (ref "MDBT1") (pin "21") (pinfunction "P0.13/QSPI0_21") (pintype "bidirectional"))
      (node (ref "U6") (pin "5") (pinfunction "D0/DI_5") (pintype "bidirectional"))
    )
    (net (code "41") (name "QSPI-1") (class "Default")
      (node (ref "MDBT1") (pin "27") (pinfunction "P0.14/QSPI1_27") (pintype "bidirectional"))
      (node (ref "U6") (pin "2") (pinfunction "D1/DO_2") (pintype "bidirectional"))
    )
    (net (code "42") (name "QSPI-2") (class "Default")
      (node (ref "MDBT1") (pin "23") (pinfunction "P0.15/QSPI2_23") (pintype "bidirectional"))
      (node (ref "U6") (pin "3") (pinfunction "D2/~{WP}_3") (pintype "bidirectional"))
    )
    (net (code "43") (name "QSPI-3") (class "Default")
      (node (ref "MDBT1") (pin "28") (pinfunction "P0.16/QSPI3_28") (pintype "bidirectional"))
      (node (ref "U6") (pin "7") (pinfunction "D3/~{HOLD}_7") (pintype "bidirectional"))
    )
    (net (code "44") (name "QSPI-CLK") (class "Default")
      (node (ref "MDBT1") (pin "26") (pinfunction "P0.17/QSPI_SCK_26") (pintype "bidirectional"))
      (node (ref "U6") (pin "6") (pinfunction "CLK_6") (pintype "bidirectional"))
    )
    (net (code "45") (name "QSPI-CS") (class "Default")
      (node (ref "MDBT1") (pin "16") (pinfunction "P0.18/QSPI_CSN_16") (pintype "bidirectional"))
      (node (ref "R22") (pin "1") (pinfunction "1_1") (pintype "passive"))
      (node (ref "U6") (pin "1") (pinfunction "~{CS}_1") (pintype "bidirectional"))
    )
    (net (code "46") (name "RESET1") (class "Default")
      (node (ref "MDBT1") (pin "6") (pinfunction "RESET_6") (pintype "bidirectional"))
      (node (ref "P1") (pin "TP") (pinfunction "TP_TP") (pintype "input"))
    )
    (net (code "47") (name "RTC_INT") (class "Default")
      (node (ref "MDBT1") (pin "35") (pinfunction "P0.06/AIN2_35") (pintype "bidirectional"))
      (node (ref "R12") (pin "1") (pinfunction "1_1") (pintype "passive"))
      (node (ref "U2") (pin "4") (pinfunction "~{INT}_4") (pintype "output"))
    )
    (net (code "48") (name "SBU") (class "Default")
      (node (ref "D8") (pin "C") (pinfunction "C_C") (pintype "passive"))
      (node (ref "R2") (pin "2") (pinfunction "2_2") (pintype "passive"))
      (node (ref "R4") (pin "2") (pinfunction "2_2") (pintype "passive"))
    )
    (net (code "49") (name "SDO") (class "Default")
      (node (ref "U$22") (pin "6") (pinfunction "P$6_6") (pintype "bidirectional"))
    )
    (net (code "50") (name "SEN_MFIO") (class "Default")
      (node (ref "J3") (pin "16") (pinfunction "16_16") (pintype "passive"))
      (node (ref "MDBT1") (pin "63") (pinfunction "P1.07_63") (pintype "bidirectional"))
    )
    (net (code "51") (name "SEN_MISO") (class "Default")
      (node (ref "J3") (pin "15") (pinfunction "15_15") (pintype "passive"))
      (node (ref "MDBT1") (pin "18") (pinfunction "P0.10/HSPI_MISO_18") (pintype "bidirectional"))
    )
    (net (code "52") (name "SEN_MOSI") (class "Default")
      (node (ref "J3") (pin "8") (pinfunction "8_8") (pintype "passive"))
      (node (ref "MDBT1") (pin "19") (pinfunction "P0.09/HSPI_MOSI_19") (pintype "bidirectional"))
    )
    (net (code "53") (name "SEN_RST") (class "Default")
      (node (ref "J3") (pin "19") (pinfunction "19_19") (pintype "passive"))
      (node (ref "MDBT1") (pin "10") (pinfunction "P1.06_10") (pintype "bidirectional"))
    )
    (net (code "54") (name "SEN_SCK") (class "Default")
      (node (ref "J3") (pin "4") (pinfunction "4_4") (pintype "passive"))
      (node (ref "MDBT1") (pin "29") (pinfunction "P0.08/HSPI_SCK_29") (pintype "bidirectional"))
    )
    (net (code "55") (name "SEN_SCL") (class "Default")
      (node (ref "J3") (pin "18") (pinfunction "18_18") (pintype "passive"))
      (node (ref "MDBT1") (pin "9") (pinfunction "P0.25/AIN4_9") (pintype "bidirectional"))
      (node (ref "RN1") (pin "3") (pinfunction "1_3") (pintype "passive"))
      (node (ref "U1") (pin "7") (pinfunction "SCL_7") (pintype "input"))
      (node (ref "U2") (pin "7") (pinfunction "SCL_7") (pintype "input"))
      (node (ref "U3") (pin "13") (pinfunction "SCL_13") (pintype "bidirectional"))
    )
    (net (code "56") (name "SEN_SDA") (class "Default")
      (node (ref "J3") (pin "17") (pinfunction "17_17") (pintype "passive"))
      (node (ref "MDBT1") (pin "8") (pinfunction "P0.24_8") (pintype "bidirectional"))
      (node (ref "RN1") (pin "2") (pinfunction "1_2") (pintype "passive"))
      (node (ref "U1") (pin "8") (pinfunction "SDA_8") (pintype "bidirectional"))
      (node (ref "U2") (pin "8") (pinfunction "SDA_8") (pintype "bidirectional"))
      (node (ref "U3") (pin "14") (pinfunction "SDA_14") (pintype "bidirectional"))
    )
    (net (code "57") (name "SW1") (class "Default")
      (node (ref "MDBT1") (pin "39") (pinfunction "P0.05/AIN1_39") (pintype "bidirectional"))
      (node (ref "R10") (pin "2") (pinfunction "2_2") (pintype "passive"))
      (node (ref "U$24") (pin "2") (pinfunction "1_2") (pintype "passive"))
    )
    (net (code "58") (name "SW3") (class "Default")
      (node (ref "MDBT1") (pin "30") (pinfunction "P0.03/NFC2_30") (pintype "bidirectional"))
      (node (ref "R8") (pin "2") (pinfunction "2_2") (pintype "passive"))
      (node (ref "U$17") (pin "2") (pinfunction "1_2") (pintype "passive"))
    )
    (net (code "59") (name "SWCLK1") (class "Default")
      (node (ref "J1") (pin "3") (pinfunction "3_3") (pintype "passive"))
      (node (ref "MDBT1") (pin "2") (pinfunction "SWDCLK_2") (pintype "bidirectional"))
      (node (ref "U4") (pin "4") (pinfunction "S2B_4") (pintype "bidirectional"))
    )
    (net (code "60") (name "SWDIO1") (class "Default")
      (node (ref "J1") (pin "4") (pinfunction "4_4") (pintype "passive"))
      (node (ref "MDBT1") (pin "4") (pinfunction "SWDIO_4") (pintype "bidirectional"))
      (node (ref "U4") (pin "1") (pinfunction "S1B_1") (pintype "bidirectional"))
    )
    (net (code "61") (name "SW_D1") (class "Default")
      (node (ref "D11") (pin "2") (pinfunction "2_2") (pintype "bidirectional"))
      (node (ref "J2") (pin "A2") (pinfunction "SSTXP1_A2") (pintype "bidirectional"))
      (node (ref "J2") (pin "B2") (pinfunction "SSTXP2_B2") (pintype "bidirectional"))
      (node (ref "U4") (pin "2") (pinfunction "D1_2") (pintype "bidirectional"))
    )
    (net (code "62") (name "SW_D2") (class "Default")
      (node (ref "D1") (pin "2") (pinfunction "2_2") (pintype "bidirectional"))
      (node (ref "J2") (pin "A3") (pinfunction "SSTXN1_A3") (pintype "bidirectional"))
      (node (ref "J2") (pin "B3") (pinfunction "SSTXN2_B3") (pintype "bidirectional"))
      (node (ref "U4") (pin "5") (pinfunction "D2_5") (pintype "bidirectional"))
    )
    (net (code "63") (name "SW_D3") (class "Default")
      (node (ref "D6") (pin "2") (pinfunction "2_2") (pintype "bidirectional"))
      (node (ref "J2") (pin "A11") (pinfunction "SSRXP2_A11") (pintype "bidirectional"))
      (node (ref "J2") (pin "B11") (pinfunction "SSRXP1_B11") (pintype "bidirectional"))
      (node (ref "U4") (pin "7") (pinfunction "D3_7") (pintype "bidirectional"))
    )
    (net (code "64") (name "SW_D4") (class "Default")
      (node (ref "D5") (pin "2") (pinfunction "2_2") (pintype "bidirectional"))
      (node (ref "J2") (pin "A10") (pinfunction "SSRXN2_A10") (pintype "bidirectional"))
      (node (ref "J2") (pin "B10") (pinfunction "SSRXN1_B10") (pintype "bidirectional"))
      (node (ref "U4") (pin "10") (pinfunction "D4_10") (pintype "bidirectional"))
    )
    (net (code "65") (name "S_INT") (class "Default")
      (node (ref "J4") (pin "8") (pinfunction "8_8") (pintype "passive"))
      (node (ref "U4") (pin "9") (pinfunction "S3A_9") (pintype "bidirectional"))
    )
    (net (code "66") (name "S_SCL") (class "Default")
      (node (ref "J4") (pin "6") (pinfunction "6_6") (pintype "passive"))
      (node (ref "U4") (pin "3") (pinfunction "S2A_3") (pintype "bidirectional"))
    )
    (net (code "67") (name "S_SDA") (class "Default")
      (node (ref "J4") (pin "4") (pinfunction "4_4") (pintype "passive"))
      (node (ref "U4") (pin "16") (pinfunction "S1A_16") (pintype "bidirectional"))
    )
    (net (code "68") (name "TFT_BL") (class "Default")
      (node (ref "MDBT1") (pin "22") (pinfunction "P1.05_22") (pintype "bidirectional"))
      (node (ref "R1") (pin "2") (pinfunction "2_2") (pintype "passive"))
    )
    (net (code "69") (name "TFT_CS") (class "Default")
      (node (ref "MDBT1") (pin "11") (pinfunction "P1.04_11") (pintype "bidirectional"))
      (node (ref "U$22") (pin "4") (pinfunction "P$4_4") (pintype "bidirectional"))
    )
    (net (code "70") (name "TFT_DC") (class "Default")
      (node (ref "MDBT1") (pin "43") (pinfunction "P1.01_43") (pintype "bidirectional"))
      (node (ref "U$22") (pin "8") (pinfunction "P$8_8") (pintype "bidirectional"))
    )
    (net (code "71") (name "TFT_MOSI") (class "Default")
      (node (ref "MDBT1") (pin "51") (pinfunction "P1.13_51") (pintype "bidirectional"))
      (node (ref "U$22") (pin "7") (pinfunction "P$7_7") (pintype "bidirectional"))
    )
    (net (code "72") (name "TFT_RST") (class "Default")
      (node (ref "MDBT1") (pin "65") (pinfunction "P0.29_65") (pintype "bidirectional"))
      (node (ref "U$22") (pin "3") (pinfunction "P$3_3") (pintype "bidirectional"))
    )
    (net (code "73") (name "TFT_SCK") (class "Default")
      (node (ref "MDBT1") (pin "47") (pinfunction "P1.15_47") (pintype "bidirectional"))
      (node (ref "U$22") (pin "5") (pinfunction "P$5_5") (pintype "bidirectional"))
    )
    (net (code "74") (name "TP_INT") (class "Default")
      (node (ref "MDBT1") (pin "7") (pinfunction "P0.26/AIN5_7") (pintype "bidirectional"))
      (node (ref "U$22") (pin "16") (pinfunction "P$16_16") (pintype "bidirectional"))
    )
    (net (code "75") (name "TP_RST") (class "Default")
      (node (ref "MDBT1") (pin "5") (pinfunction "P0.27/AIN6_5") (pintype "bidirectional"))
      (node (ref "U$22") (pin "19") (pinfunction "P$19_19") (pintype "bidirectional"))
    )
    (net (code "76") (name "TP_SCL") (class "Default")
      (node (ref "MDBT1") (pin "31") (pinfunction "P1.03/TWI_31") (pintype "bidirectional"))
      (node (ref "R9") (pin "2") (pinfunction "2_2") (pintype "passive"))
      (node (ref "U$22") (pin "17") (pinfunction "P$17_17") (pintype "bidirectional"))
    )
    (net (code "77") (name "TP_SDA") (class "Default")
      (node (ref "MDBT1") (pin "33") (pinfunction "P1.02/TWI_33") (pintype "bidirectional"))
      (node (ref "R11") (pin "2") (pinfunction "2_2") (pintype "passive"))
      (node (ref "U$22") (pin "18") (pinfunction "P$18_18") (pintype "bidirectional"))
    )
    (net (code "78") (name "UART_TX") (class "Default")
      (node (ref "J1") (pin "2") (pinfunction "2_2") (pintype "power_in"))
      (node (ref "MDBT1") (pin "13") (pinfunction "P0.20_13") (pintype "bidirectional"))
      (node (ref "TX") (pin "TP") (pinfunction "TP_TP") (pintype "input"))
      (node (ref "U4") (pin "8") (pinfunction "S3B_8") (pintype "bidirectional"))
    )
    (net (code "79") (name "USB_D+") (class "Default")
      (node (ref "MDBT1") (pin "46") (pinfunction "D+_46") (pintype "bidirectional"))
      (node (ref "R32") (pin "2") (pinfunction "2_2") (pintype "passive"))
    )
    (net (code "80") (name "USB_D-") (class "Default")
      (node (ref "MDBT1") (pin "48") (pinfunction "D-_48") (pintype "bidirectional"))
      (node (ref "R31") (pin "2") (pinfunction "2_2") (pintype "passive"))
    )
    (net (code "81") (name "VBAT") (class "Default")
      (node (ref "C3") (pin "1") (pinfunction "1_1") (pintype "passive"))
      (node (ref "D2") (pin "C") (pinfunction "C_C") (pintype "passive"))
      (node (ref "J4") (pin "5") (pinfunction "5_5") (pintype "passive"))
      (node (ref "Q1") (pin "2") (pinfunction "S_2") (pintype "passive"))
      (node (ref "U9") (pin "1") (pinfunction "IN_1") (pintype "input"))
      (node (ref "U9") (pin "3") (pinfunction "EN_3") (pintype "input"))
    )
    (net (code "82") (name "VSENSE") (class "Default")
      (node (ref "J4") (pin "1") (pinfunction "1_1") (pintype "passive"))
      (node (ref "J4") (pin "3") (pinfunction "3_3") (pintype "passive"))
      (node (ref "Q2") (pin "3") (pinfunction "D_3") (pintype "passive"))
    )
    (net (code "83") (name "VUSB2") (class "Default")
      (node (ref "C5") (pin "1") (pinfunction "1_1") (pintype "passive"))
      (node (ref "D2") (pin "A") (pinfunction "A_A") (pintype "passive"))
      (node (ref "J2") (pin "A4") (pinfunction "VBUS_A_A4") (pintype "power_in"))
      (node (ref "J2") (pin "A9") (pinfunction "VBUS_A_A9") (pintype "power_in"))
      (node (ref "J2") (pin "B4") (pinfunction "VBUS_B_B4") (pintype "power_in"))
      (node (ref "J2") (pin "B9") (pinfunction "VBUS_B_B9") (pintype "power_in"))
      (node (ref "Q1") (pin "1") (pinfunction "G_1") (pintype "passive"))
      (node (ref "Q2") (pin "1") (pinfunction "G_1") (pintype "passive"))
      (node (ref "R15") (pin "2") (pinfunction "2_2") (pintype "passive"))
      (node (ref "R29") (pin "2") (pinfunction "2_2") (pintype "passive"))
      (node (ref "R52") (pin "1") (pinfunction "1_1") (pintype "passive"))
      (node (ref "R6") (pin "1") (pinfunction "1_1") (pintype "passive"))
      (node (ref "U8") (pin "1") (pinfunction "VDD_1") (pintype "power_in"))
      (node (ref "U8") (pin "2") (pinfunction "VDD_2") (pintype "power_in"))
    )
    (net (code "84") (name "unconnected-(J3-Pad6)") (class "Default")
      (node (ref "J3") (pin "6") (pinfunction "6_6") (pintype "passive"))
    )
    (net (code "85") (name "unconnected-(J3-Pad7)") (class "Default")
      (node (ref "J3") (pin "7") (pinfunction "7_7") (pintype "passive"))
    )
    (net (code "86") (name "unconnected-(J3-Pad10)") (class "Default")
      (node (ref "J3") (pin "10") (pinfunction "10_10") (pintype "passive"))
    )
    (net (code "87") (name "unconnected-(J3-Pad12)") (class "Default")
      (node (ref "J3") (pin "12") (pinfunction "12_12") (pintype "passive"))
    )
    (net (code "88") (name "unconnected-(J3-Pad13)") (class "Default")
      (node (ref "J3") (pin "13") (pinfunction "13_13") (pintype "passive"))
    )
    (net (code "89") (name "unconnected-(J4-Pad7)") (class "Default")
      (node (ref "J4") (pin "7") (pinfunction "7_7") (pintype "passive"))
    )
    (net (code "90") (name "unconnected-(J4-Pad9)") (class "Default")
      (node (ref "J4") (pin "9") (pinfunction "9_9") (pintype "passive"))
    )
    (net (code "91") (name "unconnected-(J4-Pad10)") (class "Default")
      (node (ref "J4") (pin "10") (pinfunction "10_10") (pintype "passive"))
    )
    (net (code "92") (name "unconnected-(J4-Pad11)") (class "Default")
      (node (ref "J4") (pin "11") (pinfunction "11_11") (pintype "passive"))
    )
    (net (code "93") (name "unconnected-(J4-Pad12)") (class "Default")
      (node (ref "J4") (pin "12") (pinfunction "12_12") (pintype "passive"))
    )
    (net (code "94") (name "unconnected-(J4-Pad13)") (class "Default")
      (node (ref "J4") (pin "13") (pinfunction "13_13") (pintype "passive"))
    )
    (net (code "95") (name "unconnected-(J4-Pad14)") (class "Default")
      (node (ref "J4") (pin "14") (pinfunction "14_14") (pintype "passive"))
    )
    (net (code "96") (name "unconnected-(J4-Pad15)") (class "Default")
      (node (ref "J4") (pin "15") (pinfunction "15_15") (pintype "passive"))
    )
    (net (code "97") (name "unconnected-(J4-Pad16)") (class "Default")
      (node (ref "J4") (pin "16") (pinfunction "16_16") (pintype "passive"))
    )
    (net (code "98") (name "unconnected-(J4-Pad17)") (class "Default")
      (node (ref "J4") (pin "17") (pinfunction "17_17") (pintype "passive"))
    )
    (net (code "99") (name "unconnected-(J4-Pad18)") (class "Default")
      (node (ref "J4") (pin "18") (pinfunction "18_18") (pintype "passive"))
    )
    (net (code "100") (name "unconnected-(MDBT1-P0.02{slash}NFC1-Pad32)") (class "Default")
      (node (ref "MDBT1") (pin "32") (pinfunction "P0.02/NFC1_32") (pintype "bidirectional"))
    )
    (net (code "101") (name "unconnected-(MDBT1-P0.07{slash}AIN3-Pad20)") (class "Default")
      (node (ref "MDBT1") (pin "20") (pinfunction "P0.07/AIN3_20") (pintype "bidirectional"))
    )
    (net (code "102") (name "unconnected-(MDBT1-P0.11{slash}HSPI_CSN-Pad17)") (class "Default")
      (node (ref "MDBT1") (pin "17") (pinfunction "P0.11/HSPI_CSN_17") (pintype "bidirectional"))
    )
    (net (code "103") (name "unconnected-(MDBT1-P0.12{slash}HSPI_DCX-Pad15)") (class "Default")
      (node (ref "MDBT1") (pin "15") (pinfunction "P0.12/HSPI_DCX_15") (pintype "bidirectional"))
    )
    (net (code "104") (name "unconnected-(MDBT1-P0.23-Pad62)") (class "Default")
      (node (ref "MDBT1") (pin "62") (pinfunction "P0.23_62") (pintype "bidirectional"))
    )
    (net (code "105") (name "unconnected-(MDBT1-P0.28{slash}AIN7-Pad60)") (class "Default")
      (node (ref "MDBT1") (pin "60") (pinfunction "P0.28/AIN7_60") (pintype "bidirectional"))
    )
    (net (code "106") (name "unconnected-(MDBT1-P0.30-Pad57)") (class "Default")
      (node (ref "MDBT1") (pin "57") (pinfunction "P0.30_57") (pintype "bidirectional"))
    )
    (net (code "107") (name "unconnected-(MDBT1-P0.31-Pad56)") (class "Default")
      (node (ref "MDBT1") (pin "56") (pinfunction "P0.31_56") (pintype "bidirectional"))
    )
    (net (code "108") (name "unconnected-(MDBT1-P1.12-Pad53)") (class "Default")
      (node (ref "MDBT1") (pin "53") (pinfunction "P1.12_53") (pintype "bidirectional"))
    )
    (net (code "109") (name "unconnected-(MDBT1-P1.14-Pad49)") (class "Default")
      (node (ref "MDBT1") (pin "49") (pinfunction "P1.14_49") (pintype "bidirectional"))
    )
    (net (code "110") (name "unconnected-(U$17-0-Pad1)") (class "Default")
      (node (ref "U$17") (pin "1") (pinfunction "0_1") (pintype "passive"))
    )
    (net (code "111") (name "unconnected-(U$17-1-Pad4)") (class "Default")
      (node (ref "U$17") (pin "4") (pinfunction "1_4") (pintype "passive"))
    )
    (net (code "112") (name "unconnected-(U$24-0-Pad1)") (class "Default")
      (node (ref "U$24") (pin "1") (pinfunction "0_1") (pintype "passive"))
    )
    (net (code "113") (name "unconnected-(U$24-1-Pad4)") (class "Default")
      (node (ref "U$24") (pin "4") (pinfunction "1_4") (pintype "passive"))
    )
    (net (code "114") (name "unconnected-(U2-CLKOUT-Pad6)") (class "Default")
      (node (ref "U2") (pin "6") (pinfunction "CLKOUT_6") (pintype "output"))
    )
    (net (code "115") (name "unconnected-(U2-NC-Pad1)") (class "Default")
      (node (ref "U2") (pin "1") (pinfunction "NC_1") (pintype "no_connect"))
    )
    (net (code "116") (name "unconnected-(U3-INT2-Pad9)") (class "Default")
      (node (ref "U3") (pin "9") (pinfunction "INT2_9") (pintype "bidirectional"))
    )
    (net (code "117") (name "unconnected-(U3-NC-Pad11)") (class "Default")
      (node (ref "U3") (pin "11") (pinfunction "NC_11") (pintype "bidirectional"))
    )
    (net (code "118") (name "unconnected-(U3-OCS-Pad10)") (class "Default")
      (node (ref "U3") (pin "10") (pinfunction "OCS_10") (pintype "bidirectional"))
    )
    (net (code "119") (name "unconnected-(U4-S4A-Pad12)") (class "Default")
      (node (ref "U4") (pin "12") (pinfunction "S4A_12") (pintype "bidirectional"))
    )
    (net (code "120") (name "unconnected-(U4-S4B-Pad11)") (class "Default")
      (node (ref "U4") (pin "11") (pinfunction "S4B_11") (pintype "bidirectional"))
    )
    (net (code "121") (name "unconnected-(U9-BP-Pad4)") (class "Default")
      (node (ref "U9") (pin "4") (pinfunction "BP_4") (pintype "input"))
    )
  )
)
